# ControlBoard.net
KiCad netlist of a schematic drawn in Altium Designer
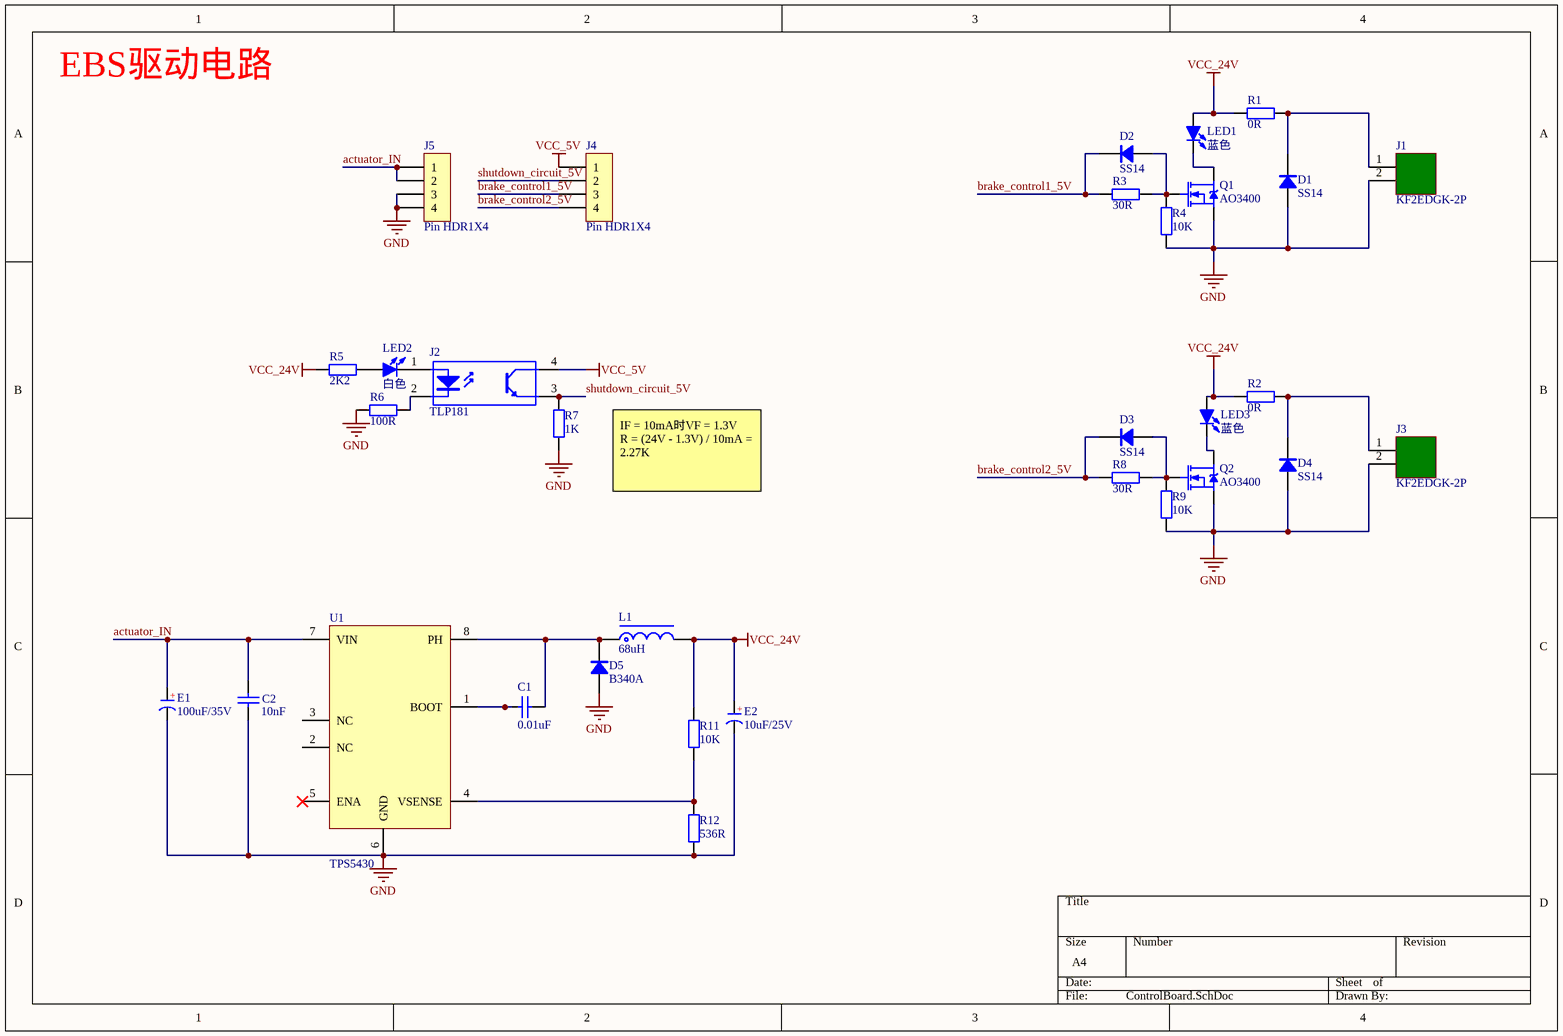
[diagram p0: ControlBoard.SchDoc]

(export (version "E")
  (design (tool "Eeschema 10.0.6"))
  (components
    (comp (ref "C1")
      (value "0.01uF")
      (footprint "C 0805_M")
      (description "无极性贴片电容")
      (libsource (lib "mainlib") (part "C"))
    )
    (comp (ref "C2")
      (value "10nF")
      (footprint "C 0805_M")
      (description "无极性贴片电容")
      (libsource (lib "mainlib") (part "C"))
    )
    (comp (ref "D1")
      (value "SS14")
      (footprint "SMA")
      (description "肖特基二极管")
      (fields (field (name "版权归属") "源创客"))
      (libsource (lib "mainlib") (part "SS14"))
    )
    (comp (ref "D2")
      (value "SS14")
      (footprint "SMA")
      (description "肖特基二极管")
      (fields (field (name "版权归属") "源创客"))
      (libsource (lib "mainlib") (part "SS14"))
    )
    (comp (ref "D3")
      (value "SS14")
      (footprint "SMA")
      (description "肖特基二极管")
      (fields (field (name "版权归属") "源创客"))
      (libsource (lib "mainlib") (part "SS14"))
    )
    (comp (ref "D4")
      (value "SS14")
      (footprint "SMA")
      (description "肖特基二极管")
      (fields (field (name "版权归属") "源创客"))
      (libsource (lib "mainlib") (part "SS14"))
    )
    (comp (ref "D5")
      (value "B340A")
      (footprint "SMA")
      (description "肖特基二极管\r\n反向耐压大于28.5V")
      (fields (field (name "版权归属") "源创客"))
      (libsource (lib "mainlib") (part "SS34"))
    )
    (comp (ref "E1")
      (value "100uF/35V")
      (footprint "CM D(6.3*7.7)")
      (description "贴片电解电容\r\nESR < 0.04R")
      (fields (field (name "版权归属") "源创客"))
      (libsource (lib "mainlib") (part "C-CM"))
    )
    (comp (ref "E2")
      (value "10uF/25V")
      (footprint "CM C(5*5.4)")
      (description "贴片电解电容\r\nESR < 0.088R\r\nV>24.0002V")
      (fields (field (name "版权归属") "源创客"))
      (libsource (lib "mainlib") (part "C-CM"))
    )
    (comp (ref "J1")
      (value "KF2EDGK-2P")
      (footprint "KF2EDGK5.08W-2P")
      (libsource (lib "mainlib") (part "KF2EDGK-2P"))
    )
    (comp (ref "J2")
      (value "TLP181")
      (footprint "SOP4")
      (description "光耦")
      (fields (field (name "版权归属") "源创客"))
      (libsource (lib "mainlib") (part "TLP181"))
    )
    (comp (ref "J3")
      (value "KF2EDGK-2P")
      (footprint "KF2EDGK5.08W-2P")
      (libsource (lib "mainlib") (part "KF2EDGK-2P"))
    )
    (comp (ref "J4")
      (value "Pin HDR1X4")
      (footprint "Pin HDR1X4/2.54mm-S")
      (libsource (lib "mainlib") (part "Pin HDR1X4"))
    )
    (comp (ref "J5")
      (value "Pin HDR1X4")
      (footprint "Pin HDR1X4/2.54mm-S")
      (libsource (lib "mainlib") (part "Pin HDR1X4"))
    )
    (comp (ref "L1")
      (value "68uH")
      (footprint "SMD,6.0*6.0")
      (description "贴片功率电感\r\nIrms>0.500003A\r\nIpk>0.563A")
      (fields (field (name "版权归属") "源创客"))
      (libsource (lib "mainlib") (part "L-CD"))
    )
    (comp (ref "LED1")
      (value "蓝色")
      (footprint "LED 0805B")
      (description "贴片LED")
      (fields (field (name "版权归属") "源创客"))
      (libsource (lib "mainlib") (part "LED-SMD"))
    )
    (comp (ref "LED2")
      (value "白色")
      (footprint "LED 0805W")
      (description "贴片LED")
      (fields (field (name "版权归属") "源创客"))
      (libsource (lib "mainlib") (part "LED-SMD"))
    )
    (comp (ref "LED3")
      (value "蓝色")
      (footprint "LED 0805B")
      (description "贴片LED")
      (fields (field (name "版权归属") "源创客"))
      (libsource (lib "mainlib") (part "LED-SMD"))
    )
    (comp (ref "Q1")
      (value "AO3400")
      (footprint "SOT23")
      (description "N沟道场效应管")
      (libsource (lib "mainlib") (part "N-MOS"))
    )
    (comp (ref "Q2")
      (value "AO3400")
      (footprint "SOT23")
      (description "N沟道场效应管")
      (libsource (lib "mainlib") (part "N-MOS"))
    )
    (comp (ref "R1")
      (value "0R")
      (footprint "0805R")
      (description "贴片电阻")
      (libsource (lib "mainlib") (part "RES"))
    )
    (comp (ref "R2")
      (value "0R")
      (footprint "0805R")
      (description "贴片电阻")
      (libsource (lib "mainlib") (part "RES"))
    )
    (comp (ref "R3")
      (value "30R")
      (footprint "0805R")
      (description "贴片电阻")
      (libsource (lib "mainlib") (part "RES"))
    )
    (comp (ref "R4")
      (value "10K")
      (footprint "0805R")
      (description "贴片电阻")
      (libsource (lib "") (part "RES_2"))
    )
    (comp (ref "R5")
      (value "2K2")
      (footprint "0805R")
      (description "贴片电阻")
      (libsource (lib "mainlib") (part "RES"))
    )
    (comp (ref "R6")
      (value "100R")
      (footprint "0805R")
      (description "贴片电阻")
      (libsource (lib "mainlib") (part "RES"))
    )
    (comp (ref "R7")
      (value "1K")
      (footprint "0805R")
      (description "贴片电阻")
      (libsource (lib "") (part "RES_2"))
    )
    (comp (ref "R8")
      (value "30R")
      (footprint "0805R")
      (description "贴片电阻")
      (libsource (lib "mainlib") (part "RES"))
    )
    (comp (ref "R9")
      (value "10K")
      (footprint "0805R")
      (description "贴片电阻")
      (libsource (lib "") (part "RES_2"))
    )
    (comp (ref "R11")
      (value "10K")
      (footprint "0805R")
      (description "贴片电阻")
      (libsource (lib "") (part "RES_1"))
    )
    (comp (ref "R12")
      (value "536R")
      (footprint "0805R")
      (description "贴片电阻")
      (libsource (lib "") (part "RES_1"))
    )
    (comp (ref "U1")
      (value "TPS5430")
      (footprint "SOP8-Pad")
      (description "DCDC降压芯片")
      (libsource (lib "mainlib") (part "TPS5430"))
    )
  )
  (nets
    (net (code "1") (name "/actuator_IN") (class "Default")
      (node (ref "C2") (pin "1") (pinfunction "1_1") (pintype "passive"))
      (node (ref "E1") (pin "1") (pinfunction "A_1") (pintype "passive"))
      (node (ref "J5") (pin "1") (pinfunction "1_1") (pintype "passive"))
      (node (ref "J5") (pin "2") (pinfunction "2_2") (pintype "passive"))
      (node (ref "U1") (pin "7") (pinfunction "VIN_7") (pintype "passive"))
    )
    (net (code "2") (name "/brake_control1_5V") (class "Default")
      (node (ref "D2") (pin "2") (pinfunction "K_2") (pintype "passive"))
      (node (ref "J4") (pin "3") (pinfunction "3_3") (pintype "passive"))
      (node (ref "R3") (pin "2") (pinfunction "2_2") (pintype "passive"))
    )
    (net (code "3") (name "/brake_control2_5V") (class "Default")
      (node (ref "D3") (pin "2") (pinfunction "K_2") (pintype "passive"))
      (node (ref "J4") (pin "4") (pinfunction "4_4") (pintype "passive"))
      (node (ref "R8") (pin "2") (pinfunction "2_2") (pintype "passive"))
    )
    (net (code "4") (name "/shutdown_circuit_5V") (class "Default")
      (node (ref "J2") (pin "3") (pinfunction "E_3") (pintype "passive"))
      (node (ref "J4") (pin "2") (pinfunction "2_2") (pintype "passive"))
      (node (ref "R7") (pin "1") (pinfunction "1_1") (pintype "passive"))
    )
    (net (code "5") (name "GND") (class "Default")
      (node (ref "C2") (pin "2") (pinfunction "2_2") (pintype "passive"))
      (node (ref "D1") (pin "1") (pinfunction "A_1") (pintype "passive"))
      (node (ref "D4") (pin "1") (pinfunction "A_1") (pintype "passive"))
      (node (ref "D5") (pin "1") (pinfunction "A_1") (pintype "passive"))
      (node (ref "E1") (pin "2") (pinfunction "K_2") (pintype "passive"))
      (node (ref "E2") (pin "2") (pinfunction "K_2") (pintype "passive"))
      (node (ref "J1") (pin "2") (pinfunction "2_2") (pintype "passive"))
      (node (ref "J3") (pin "2") (pinfunction "2_2") (pintype "passive"))
      (node (ref "J5") (pin "3") (pinfunction "3_3") (pintype "passive"))
      (node (ref "J5") (pin "4") (pinfunction "4_4") (pintype "passive"))
      (node (ref "Q1") (pin "S") (pinfunction "S_S") (pintype "passive"))
      (node (ref "Q2") (pin "S") (pinfunction "S_S") (pintype "passive"))
      (node (ref "R12") (pin "1") (pinfunction "1_1") (pintype "passive"))
      (node (ref "R4") (pin "2") (pinfunction "2_2") (pintype "passive"))
      (node (ref "R6") (pin "2") (pinfunction "2_2") (pintype "passive"))
      (node (ref "R7") (pin "2") (pinfunction "2_2") (pintype "passive"))
      (node (ref "R9") (pin "2") (pinfunction "2_2") (pintype "passive"))
      (node (ref "U1") (pin "6") (pinfunction "GND_6") (pintype "passive"))
    )
    (net (code "6") (name "Net-(D1-K)") (class "Default")
      (node (ref "D1") (pin "2") (pinfunction "K_2") (pintype "passive"))
      (node (ref "J1") (pin "1") (pinfunction "1_1") (pintype "passive"))
      (node (ref "R1") (pin "1") (pinfunction "1_1") (pintype "passive"))
    )
    (net (code "7") (name "Net-(D2-A)") (class "Default")
      (node (ref "D2") (pin "1") (pinfunction "A_1") (pintype "passive"))
      (node (ref "Q1") (pin "G") (pinfunction "G_G") (pintype "passive"))
      (node (ref "R3") (pin "1") (pinfunction "1_1") (pintype "passive"))
      (node (ref "R4") (pin "1") (pinfunction "1_1") (pintype "passive"))
    )
    (net (code "8") (name "Net-(D3-A)") (class "Default")
      (node (ref "D3") (pin "1") (pinfunction "A_1") (pintype "passive"))
      (node (ref "Q2") (pin "G") (pinfunction "G_G") (pintype "passive"))
      (node (ref "R8") (pin "1") (pinfunction "1_1") (pintype "passive"))
      (node (ref "R9") (pin "1") (pinfunction "1_1") (pintype "passive"))
    )
    (net (code "9") (name "Net-(D4-K)") (class "Default")
      (node (ref "D4") (pin "2") (pinfunction "K_2") (pintype "passive"))
      (node (ref "J3") (pin "1") (pinfunction "1_1") (pintype "passive"))
      (node (ref "R2") (pin "1") (pinfunction "1_1") (pintype "passive"))
    )
    (net (code "10") (name "Net-(D5-K)") (class "Default")
      (node (ref "C1") (pin "2") (pinfunction "2_2") (pintype "passive"))
      (node (ref "D5") (pin "2") (pinfunction "K_2") (pintype "passive"))
      (node (ref "L1") (pin "1") (pinfunction "1_1") (pintype "passive"))
      (node (ref "U1") (pin "8") (pinfunction "PH_8") (pintype "passive"))
    )
    (net (code "11") (name "Net-(J2-A)") (class "Default")
      (node (ref "J2") (pin "1") (pinfunction "A_1") (pintype "passive"))
      (node (ref "LED2") (pin "2") (pinfunction "K_2") (pintype "passive"))
    )
    (net (code "12") (name "Net-(J2-K)") (class "Default")
      (node (ref "J2") (pin "2") (pinfunction "K_2") (pintype "passive"))
      (node (ref "R6") (pin "1") (pinfunction "1_1") (pintype "passive"))
    )
    (net (code "13") (name "Net-(LED1-K)") (class "Default")
      (node (ref "LED1") (pin "2") (pinfunction "K_2") (pintype "passive"))
      (node (ref "Q1") (pin "D") (pinfunction "D_D") (pintype "passive"))
    )
    (net (code "14") (name "Net-(LED2-A)") (class "Default")
      (node (ref "LED2") (pin "1") (pinfunction "A_1") (pintype "passive"))
      (node (ref "R5") (pin "1") (pinfunction "1_1") (pintype "passive"))
    )
    (net (code "15") (name "Net-(LED3-K)") (class "Default")
      (node (ref "LED3") (pin "2") (pinfunction "K_2") (pintype "passive"))
      (node (ref "Q2") (pin "D") (pinfunction "D_D") (pintype "passive"))
    )
    (net (code "16") (name "Net-(U1-BOOT)") (class "Default")
      (node (ref "C1") (pin "1") (pinfunction "1_1") (pintype "passive"))
      (node (ref "U1") (pin "1") (pinfunction "BOOT_1") (pintype "passive"))
    )
    (net (code "17") (name "Net-(U1-VSENSE)") (class "Default")
      (node (ref "R11") (pin "1") (pinfunction "1_1") (pintype "passive"))
      (node (ref "R12") (pin "2") (pinfunction "2_2") (pintype "passive"))
      (node (ref "U1") (pin "4") (pinfunction "VSENSE_4") (pintype "passive"))
    )
    (net (code "18") (name "VCC_5V") (class "Default")
      (node (ref "J2") (pin "4") (pinfunction "C_4") (pintype "passive"))
      (node (ref "J4") (pin "1") (pinfunction "1_1") (pintype "passive"))
    )
    (net (code "19") (name "VCC_24V") (class "Default")
      (node (ref "E2") (pin "1") (pinfunction "A_1") (pintype "passive"))
      (node (ref "L1") (pin "2") (pinfunction "2_2") (pintype "passive"))
      (node (ref "LED1") (pin "1") (pinfunction "A_1") (pintype "passive"))
      (node (ref "LED3") (pin "1") (pinfunction "A_1") (pintype "passive"))
      (node (ref "R1") (pin "2") (pinfunction "2_2") (pintype "passive"))
      (node (ref "R11") (pin "2") (pinfunction "2_2") (pintype "passive"))
      (node (ref "R2") (pin "2") (pinfunction "2_2") (pintype "passive"))
      (node (ref "R5") (pin "2") (pinfunction "2_2") (pintype "passive"))
    )
    (net (code "20") (name "unconnected-(U1-ENA-Pad5)") (class "Default")
      (node (ref "U1") (pin "5") (pinfunction "ENA_5") (pintype "passive+no_connect"))
    )
    (net (code "21") (name "unconnected-(U1-NC-Pad2)") (class "Default")
      (node (ref "U1") (pin "2") (pinfunction "NC_2") (pintype "passive"))
    )
    (net (code "22") (name "unconnected-(U1-NC-Pad3)") (class "Default")
      (node (ref "U1") (pin "3") (pinfunction "NC_3") (pintype "passive"))
    )
  )
)
